# fuse.net
KiCad netlist of a schematic drawn in Altium Designer
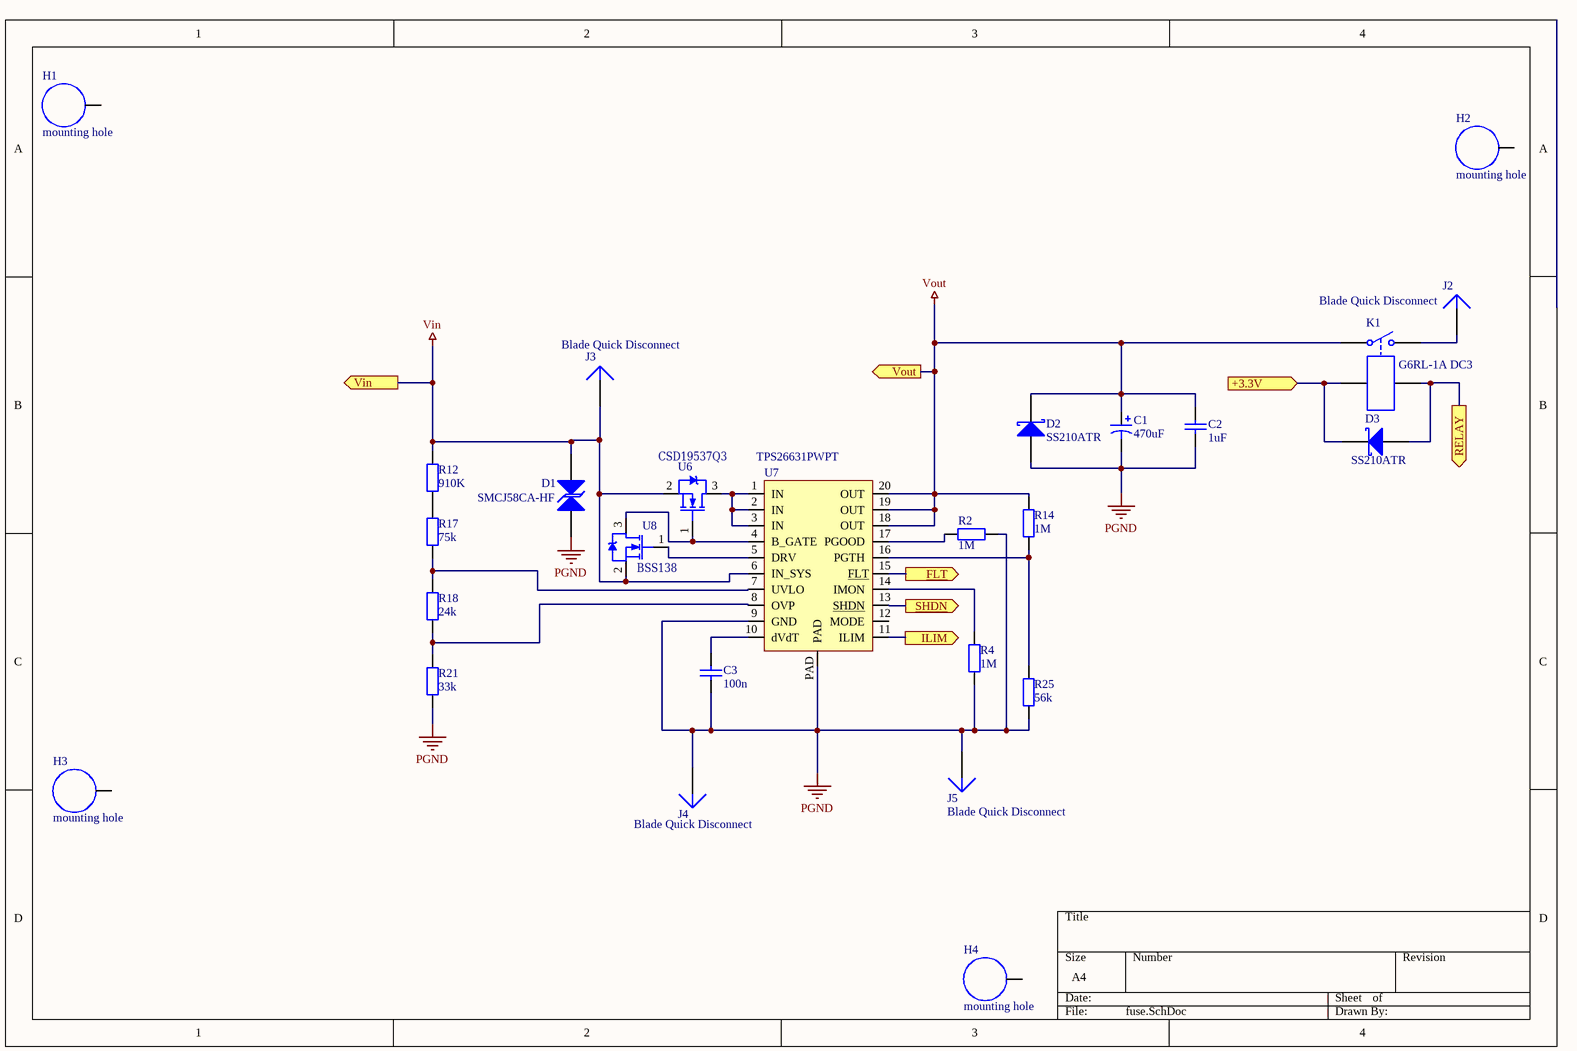
[diagram p0: fuse.SchDoc]

(export (version "E")
  (design (tool "Eeschema 10.0.6"))
  (components
    (comp (ref "C1")
      (value "470uF")
      (footprint "CAP_16MM_SMD")
      (libsource (lib "generic_components") (part "cap pol"))
    )
    (comp (ref "C2") (value "1uF") (footprint "0805") (libsource (lib "generic_components") (part "cap")))
    (comp (ref "C3") (value "100n") (footprint "0805") (libsource (lib "generic_components") (part "cap")))
    (comp (ref "D1")
      (value "SMCJ58CA-HF")
      (footprint "DO-214AB-SMC Bipolar")
      (libsource (lib "generic_components") (part "TVS Diode"))
    )
    (comp (ref "D2")
      (value "SS210ATR")
      (footprint "DO-214AC, SMA")
      (libsource (lib "generic_components") (part "shotkey diode"))
    )
    (comp (ref "D3")
      (value "SS210ATR")
      (footprint "DO-214AC, SMA")
      (libsource (lib "generic_components") (part "shotkey diode"))
    )
    (comp (ref "H1")
      (value "mounting hole")
      (footprint "M3 HOLE iso")
      (libsource (lib "generic_components") (part "mounting hole"))
    )
    (comp (ref "H2")
      (value "mounting hole")
      (footprint "M3 HOLE iso")
      (libsource (lib "generic_components") (part "mounting hole"))
    )
    (comp (ref "H3")
      (value "mounting hole")
      (footprint "M3 HOLE iso")
      (libsource (lib "generic_components") (part "mounting hole"))
    )
    (comp (ref "H4")
      (value "mounting hole")
      (footprint "M3 HOLE iso")
      (libsource (lib "generic_components") (part "mounting hole"))
    )
    (comp (ref "J2")
      (value "Blade Quick Disconnect")
      (footprint "TE blade connector")
      (libsource (lib "generic_conn") (part "Blade Quick Disconnect"))
    )
    (comp (ref "J3")
      (value "Blade Quick Disconnect")
      (footprint "TE blade connector")
      (libsource (lib "generic_conn") (part "Blade Quick Disconnect"))
    )
    (comp (ref "J4")
      (value "Blade Quick Disconnect")
      (footprint "TE blade connector")
      (libsource (lib "generic_conn") (part "Blade Quick Disconnect"))
    )
    (comp (ref "J5")
      (value "Blade Quick Disconnect")
      (footprint "TE blade connector")
      (libsource (lib "generic_conn") (part "Blade Quick Disconnect"))
    )
    (comp (ref "K1")
      (value "G6RL-1A DC3")
      (footprint "G6RL-1A DC3 relay")
      (libsource (lib "generic_components") (part "Relay"))
    )
    (comp (ref "R2") (value "1M") (footprint "0805") (libsource (lib "") (part "res0805_1")))
    (comp (ref "R4") (value "1M") (footprint "0805") (libsource (lib "") (part "res0805_2")))
    (comp (ref "R12")
      (value "910K")
      (footprint "0805")
      (libsource (lib "generic_components") (part "res0805"))
    )
    (comp (ref "R14") (value "1M") (footprint "0805") (libsource (lib "generic_components") (part "res0805")))
    (comp (ref "R17")
      (value "75k")
      (footprint "0805")
      (libsource (lib "generic_components") (part "res0805"))
    )
    (comp (ref "R18")
      (value "24k")
      (footprint "0805")
      (libsource (lib "generic_components") (part "res0805"))
    )
    (comp (ref "R21")
      (value "33k")
      (footprint "0805")
      (libsource (lib "generic_components") (part "res0805"))
    )
    (comp (ref "R25")
      (value "56k")
      (footprint "0805")
      (libsource (lib "generic_components") (part "res0805"))
    )
    (comp (ref "U6")
      (value "‎CSD19537Q3‎")
      (footprint "8-VSON (3,3x3,3)")
      (libsource (lib "generic_components") (part "N-mosfet en"))
    )
    (comp (ref "U7")
      (value "TPS26631PWPT")
      (footprint "TSSOP_P065S6.6x6.6")
      (libsource (lib "ti") (part "TPS26631PWPT"))
    )
    (comp (ref "U8")
      (value "BSS138‎")
      (footprint "SOT-23-3")
      (libsource (lib "generic_components") (part "N-mosfet en"))
    )
  )
  (nets
    (net (code "1") (name "/+3.3V") (class "Default")
      (node (ref "D3") (pin "1") (pinfunction "K_1") (pintype "passive"))
      (node (ref "K1") (pin "1") (pinfunction "1_1") (pintype "passive"))
    )
    (net (code "2") (name "/FLT") (class "Default")
      (node (ref "U7") (pin "15") (pinfunction "FLT_15") (pintype "passive"))
    )
    (net (code "3") (name "/ILIM") (class "Default")
      (node (ref "U7") (pin "11") (pinfunction "ILIM_11") (pintype "passive"))
    )
    (net (code "4") (name "/RELAY") (class "Default")
      (node (ref "D3") (pin "2") (pinfunction "A_2") (pintype "passive"))
      (node (ref "K1") (pin "5") (pinfunction "5_5") (pintype "passive"))
    )
    (net (code "5") (name "/SHDN") (class "Default")
      (node (ref "U7") (pin "13") (pinfunction "SHDN_13") (pintype "passive"))
    )
    (net (code "6") (name "Net-(J2-Pad1)") (class "Default")
      (node (ref "J2") (pin "1") (pinfunction "1_1") (pintype "passive"))
      (node (ref "K1") (pin "3") (pinfunction "3_3") (pintype "passive"))
    )
    (net (code "7") (name "Net-(R12-Pad1)") (class "Default")
      (node (ref "R12") (pin "1") (pintype "passive"))
      (node (ref "R17") (pin "2") (pinfunction "2_2") (pintype "passive"))
    )
    (net (code "8") (name "Net-(U6-G)") (class "Default")
      (node (ref "U6") (pin "1") (pinfunction "G_1") (pintype "passive"))
      (node (ref "U7") (pin "4") (pinfunction "B_GATE_4") (pintype "passive"))
      (node (ref "U8") (pin "3") (pinfunction "S_3") (pintype "passive"))
    )
    (net (code "9") (name "Net-(U6-S)") (class "Default")
      (node (ref "U6") (pin "3") (pinfunction "S_3") (pintype "passive"))
      (node (ref "U7") (pin "1") (pinfunction "IN_1") (pintype "passive"))
      (node (ref "U7") (pin "2") (pinfunction "IN_2") (pintype "passive"))
      (node (ref "U7") (pin "3") (pinfunction "IN_3") (pintype "passive"))
    )
    (net (code "10") (name "Net-(U7-DRV)") (class "Default")
      (node (ref "U7") (pin "5") (pinfunction "DRV_5") (pintype "passive"))
      (node (ref "U8") (pin "1") (pinfunction "G_1") (pintype "passive"))
    )
    (net (code "11") (name "Net-(U7-IMON)") (class "Default")
      (node (ref "R4") (pin "1") (pintype "passive"))
      (node (ref "U7") (pin "14") (pinfunction "IMON_14") (pintype "passive"))
    )
    (net (code "12") (name "Net-(U7-OVP)") (class "Default")
      (node (ref "R18") (pin "1") (pintype "passive"))
      (node (ref "R21") (pin "2") (pinfunction "2_2") (pintype "passive"))
      (node (ref "U7") (pin "8") (pinfunction "OVP_8") (pintype "passive"))
    )
    (net (code "13") (name "Net-(U7-PGOOD)") (class "Default")
      (node (ref "R2") (pin "2") (pinfunction "2_2") (pintype "passive"))
      (node (ref "U7") (pin "17") (pinfunction "PGOOD_17") (pintype "passive"))
    )
    (net (code "14") (name "Net-(U7-PGTH)") (class "Default")
      (node (ref "R14") (pin "1") (pintype "passive"))
      (node (ref "R25") (pin "2") (pinfunction "2_2") (pintype "passive"))
      (node (ref "U7") (pin "16") (pinfunction "PGTH_16") (pintype "passive"))
    )
    (net (code "15") (name "Net-(U7-UVLO)") (class "Default")
      (node (ref "R17") (pin "1") (pintype "passive"))
      (node (ref "R18") (pin "2") (pinfunction "2_2") (pintype "passive"))
      (node (ref "U7") (pin "7") (pinfunction "UVLO_7") (pintype "passive"))
    )
    (net (code "16") (name "Net-(U7-dVdT)") (class "Default")
      (node (ref "C3") (pin "1") (pinfunction "1_1") (pintype "passive"))
      (node (ref "U7") (pin "10") (pinfunction "dVdT_10") (pintype "passive"))
    )
    (net (code "17") (name "PGND") (class "Default")
      (node (ref "C1") (pin "2") (pinfunction "2_2") (pintype "passive"))
      (node (ref "C2") (pin "1") (pinfunction "1_1") (pintype "passive"))
      (node (ref "C3") (pin "2") (pinfunction "2_2") (pintype "passive"))
      (node (ref "D1") (pin "1") (pinfunction "A_1") (pintype "passive"))
      (node (ref "D2") (pin "2") (pinfunction "A_2") (pintype "passive"))
      (node (ref "J4") (pin "1") (pinfunction "1_1") (pintype "passive"))
      (node (ref "J5") (pin "1") (pinfunction "1_1") (pintype "passive"))
      (node (ref "R2") (pin "1") (pintype "passive"))
      (node (ref "R21") (pin "1") (pintype "passive"))
      (node (ref "R25") (pin "1") (pintype "passive"))
      (node (ref "R4") (pin "2") (pinfunction "2_2") (pintype "passive"))
      (node (ref "U7") (pin "9") (pinfunction "GND_9") (pintype "passive"))
      (node (ref "U7") (pin "PAD") (pinfunction "PAD_PAD") (pintype "passive"))
    )
    (net (code "18") (name "Vin") (class "Default")
      (node (ref "D1") (pin "2") (pinfunction "K_2") (pintype "passive"))
      (node (ref "J3") (pin "1") (pinfunction "1_1") (pintype "passive"))
      (node (ref "R12") (pin "2") (pinfunction "2_2") (pintype "passive"))
      (node (ref "U6") (pin "2") (pinfunction "D_2") (pintype "passive"))
      (node (ref "U7") (pin "6") (pinfunction "IN_SYS_6") (pintype "passive"))
      (node (ref "U8") (pin "2") (pinfunction "D_2") (pintype "passive"))
    )
    (net (code "19") (name "Vout") (class "Default")
      (node (ref "C1") (pin "1") (pinfunction "1_1") (pintype "passive"))
      (node (ref "C2") (pin "2") (pinfunction "2_2") (pintype "passive"))
      (node (ref "D2") (pin "1") (pinfunction "K_1") (pintype "passive"))
      (node (ref "K1") (pin "2") (pinfunction "2_2") (pintype "passive"))
      (node (ref "R14") (pin "2") (pinfunction "2_2") (pintype "passive"))
      (node (ref "U7") (pin "18") (pinfunction "OUT_18") (pintype "passive"))
      (node (ref "U7") (pin "19") (pinfunction "OUT_19") (pintype "passive"))
      (node (ref "U7") (pin "20") (pinfunction "OUT_20") (pintype "passive"))
    )
    (net (code "20") (name "unconnected-(H1-Pad1)") (class "Default")
      (node (ref "H1") (pin "1") (pintype "passive"))
    )
    (net (code "21") (name "unconnected-(H2-Pad1)") (class "Default")
      (node (ref "H2") (pin "1") (pintype "passive"))
    )
    (net (code "22") (name "unconnected-(H3-Pad1)") (class "Default")
      (node (ref "H3") (pin "1") (pintype "passive"))
    )
    (net (code "23") (name "unconnected-(H4-Pad1)") (class "Default")
      (node (ref "H4") (pin "1") (pintype "passive"))
    )
    (net (code "24") (name "unconnected-(U7-MODE-Pad12)") (class "Default")
      (node (ref "U7") (pin "12") (pinfunction "MODE_12") (pintype "passive"))
    )
  )
)
